# 0146_MTG_HOLES_AND_LABE.net
KiCad netlist of a schematic drawn in Altium Designer
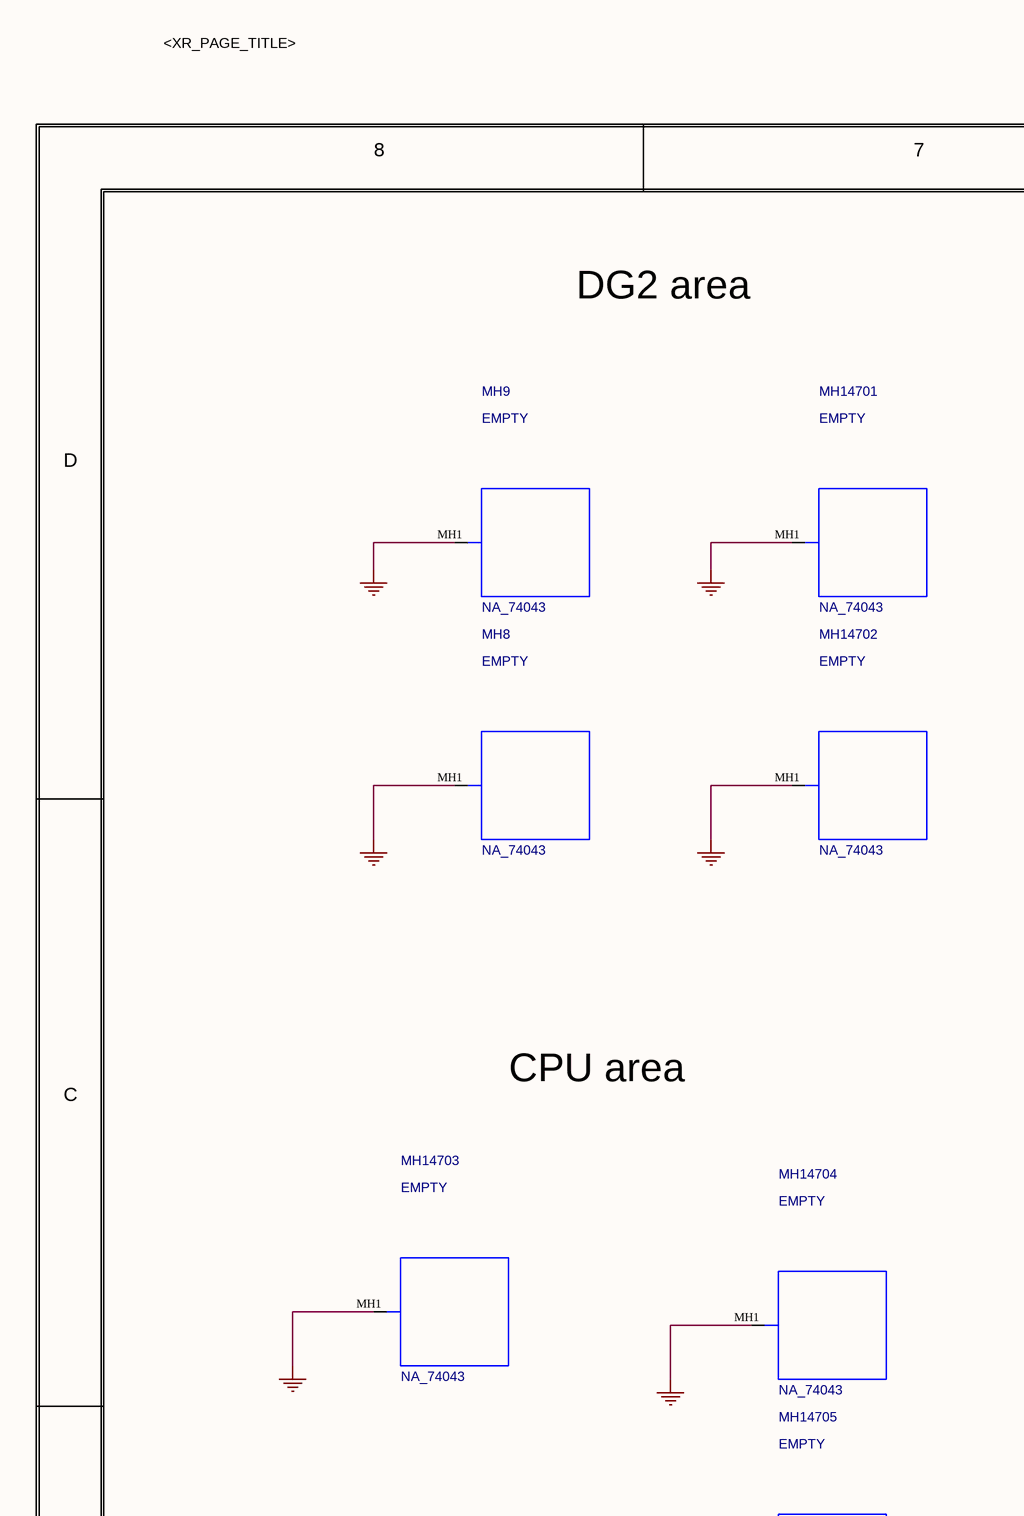
[diagram p0: 0146_MTG HOLES AND LABE.SchDoc, top left]
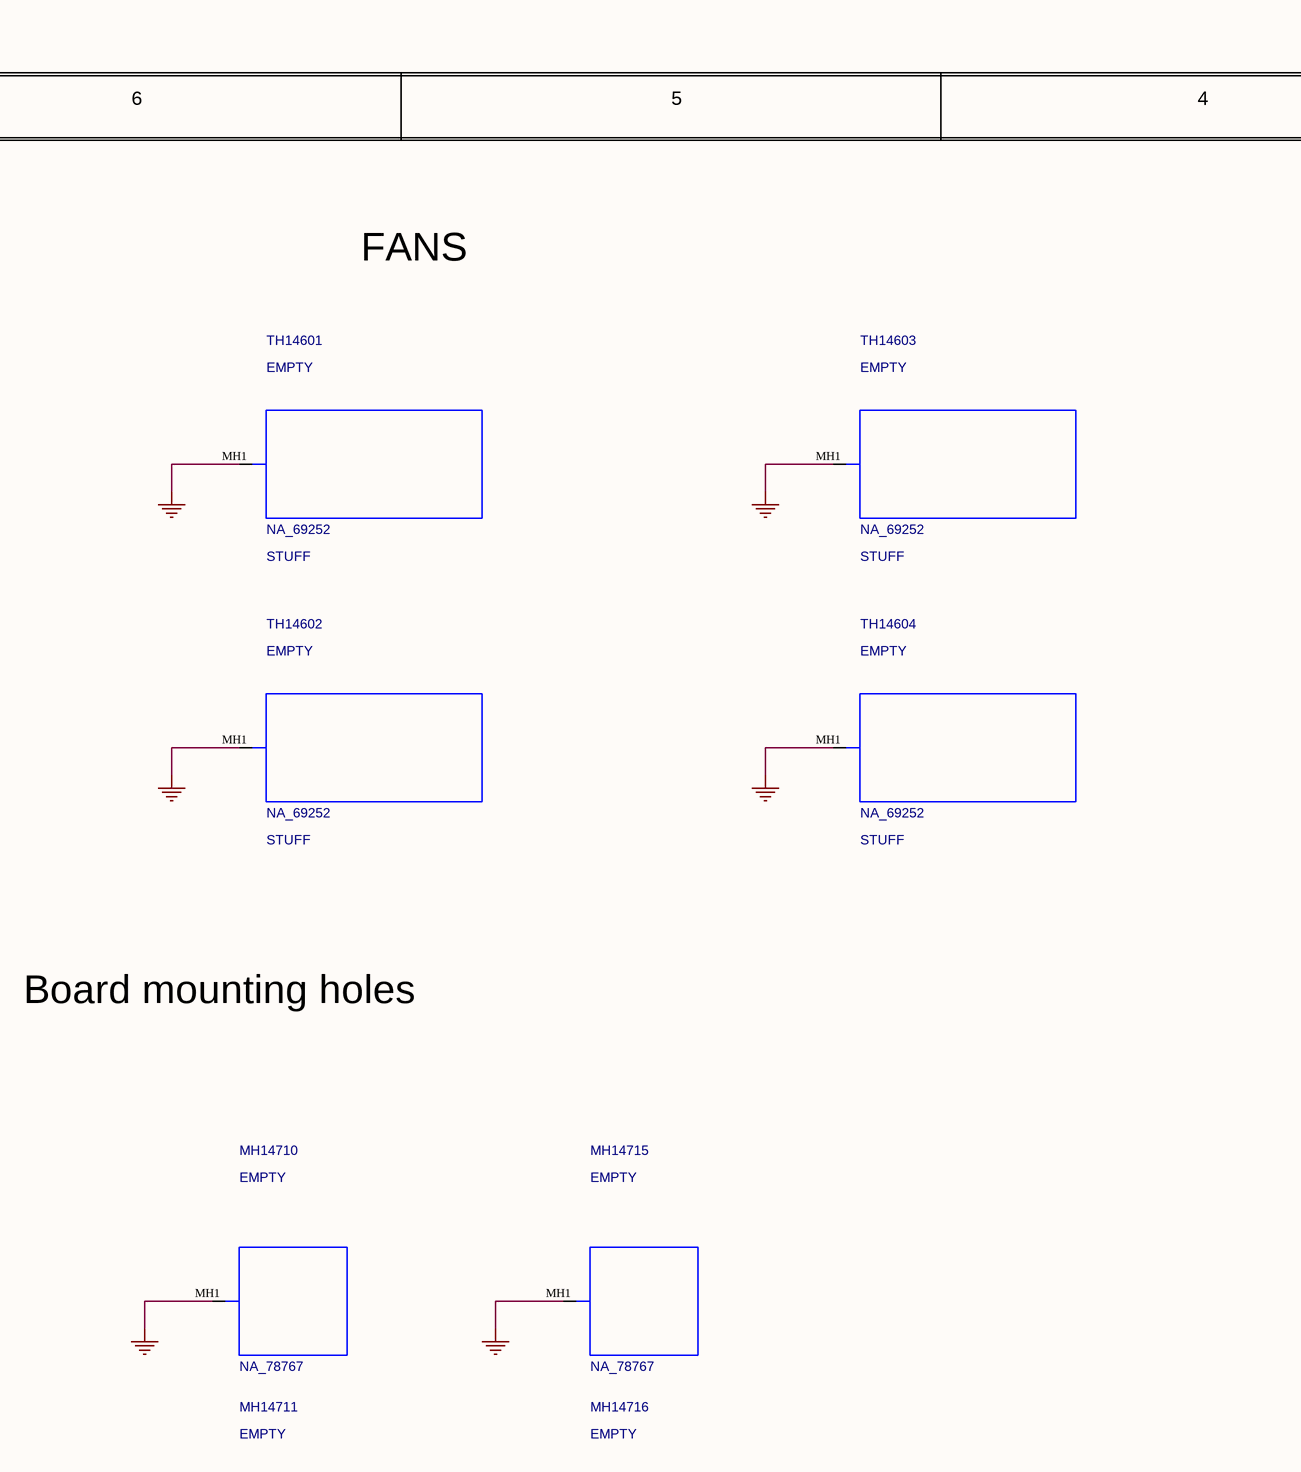
[diagram p1: 0146_MTG HOLES AND LABE.SchDoc, top middle]
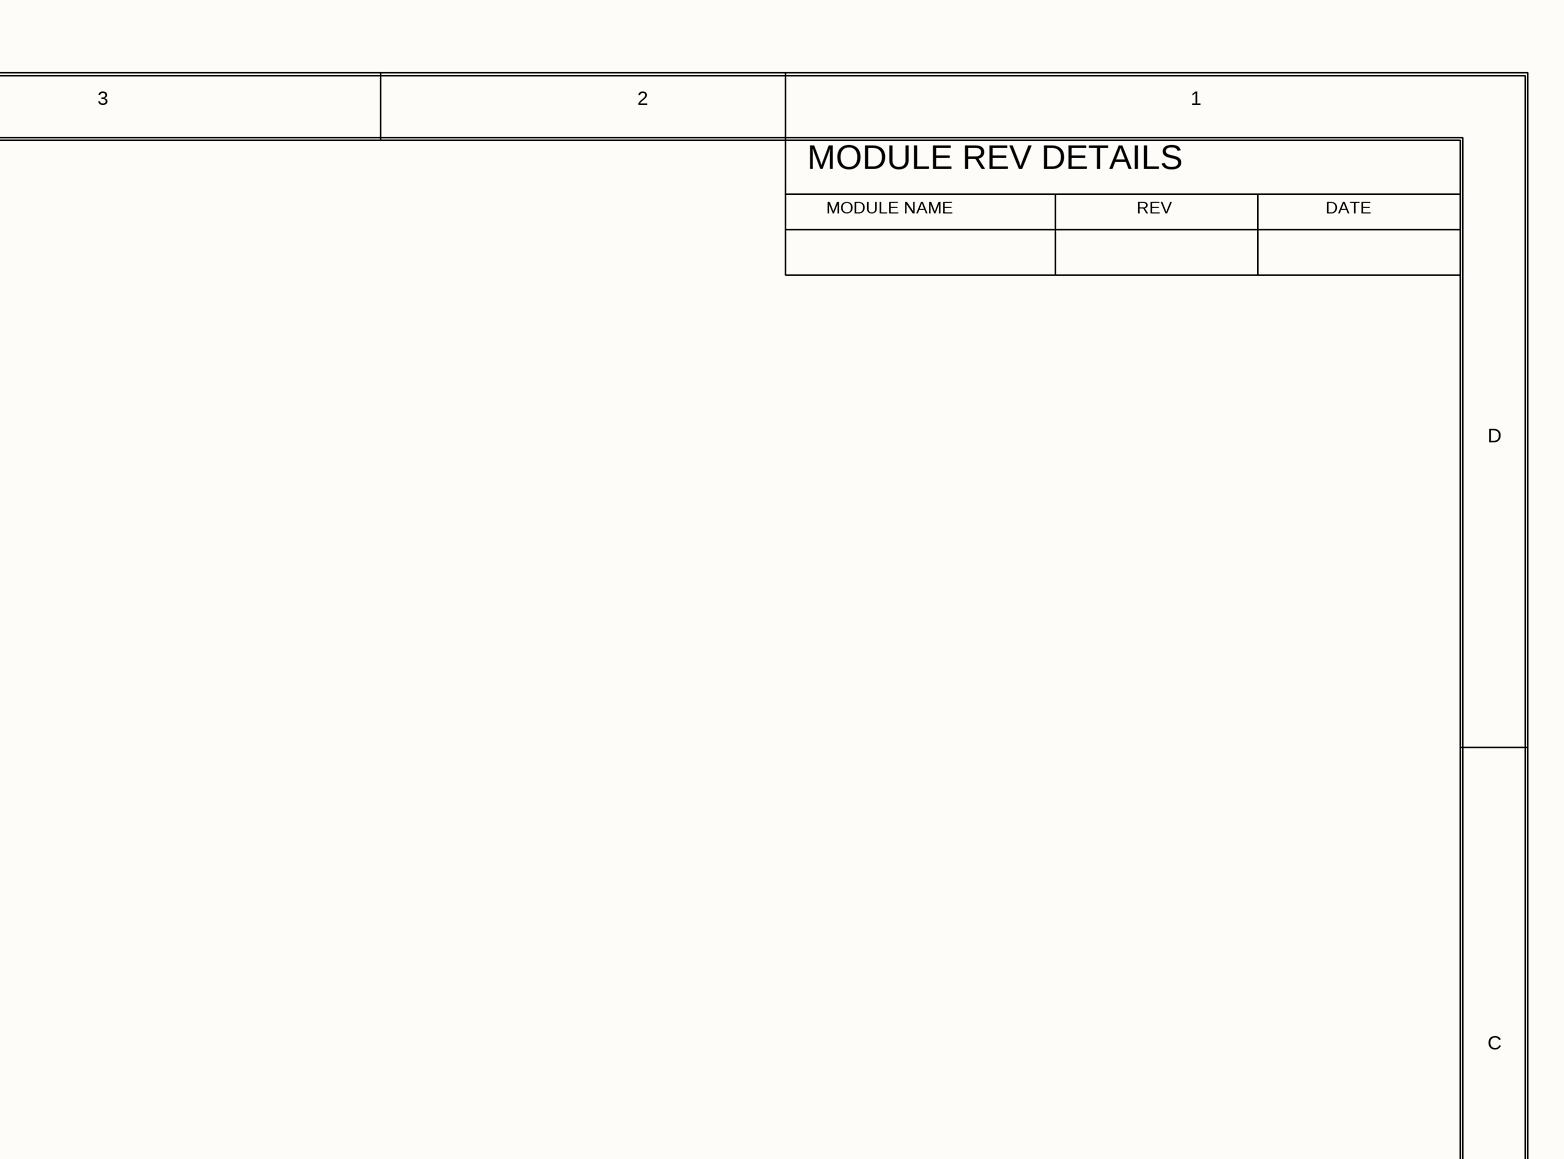
[diagram p2: 0146_MTG HOLES AND LABE.SchDoc, top right]
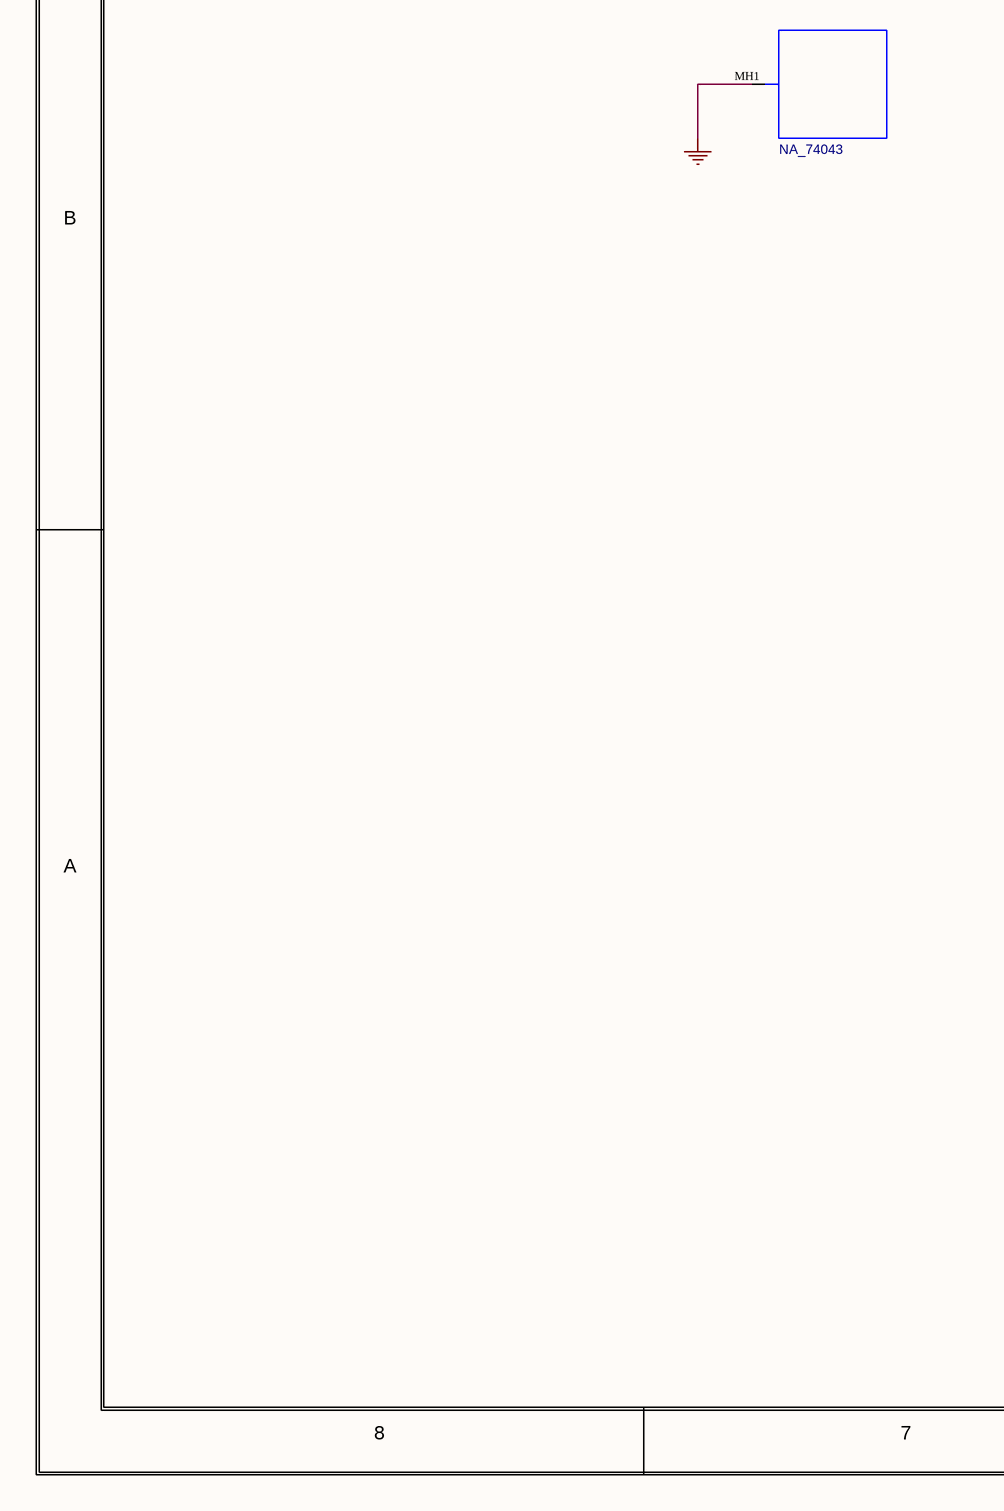
[diagram p3: 0146_MTG HOLES AND LABE.SchDoc, bottom left]
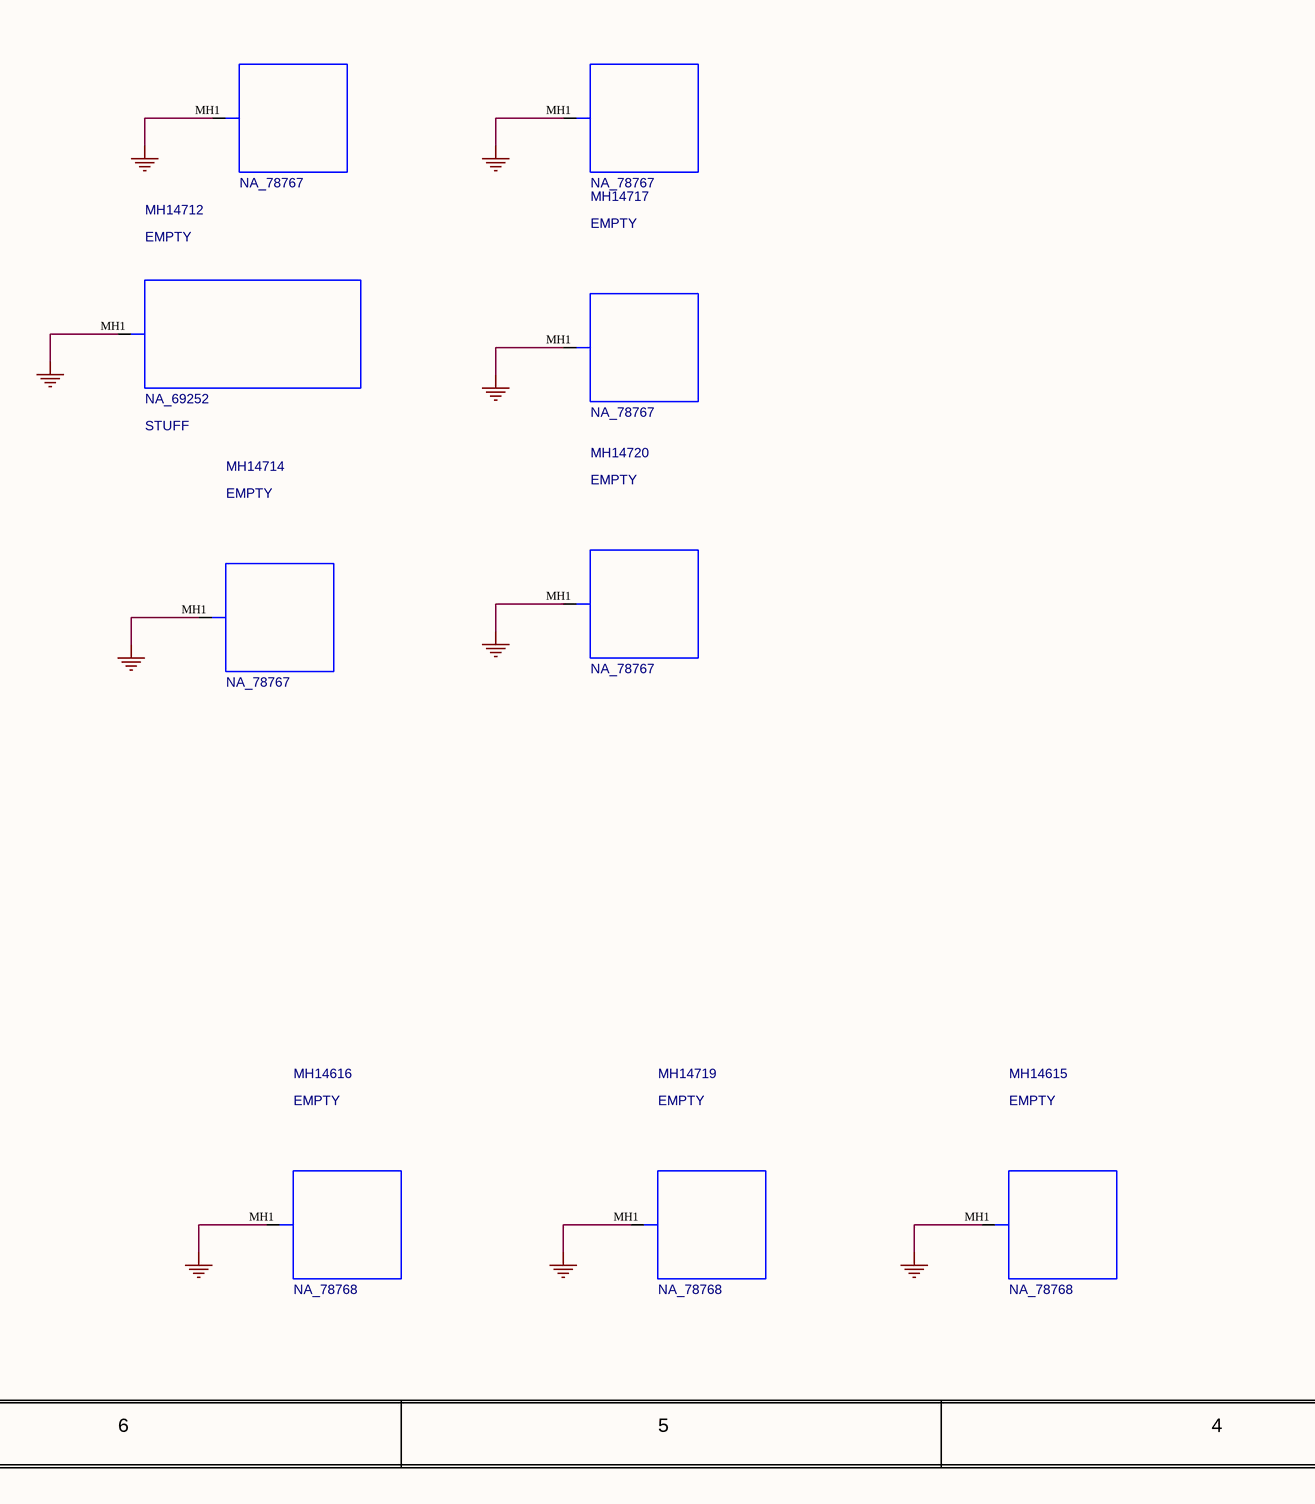
[diagram p4: 0146_MTG HOLES AND LABE.SchDoc, bottom middle]
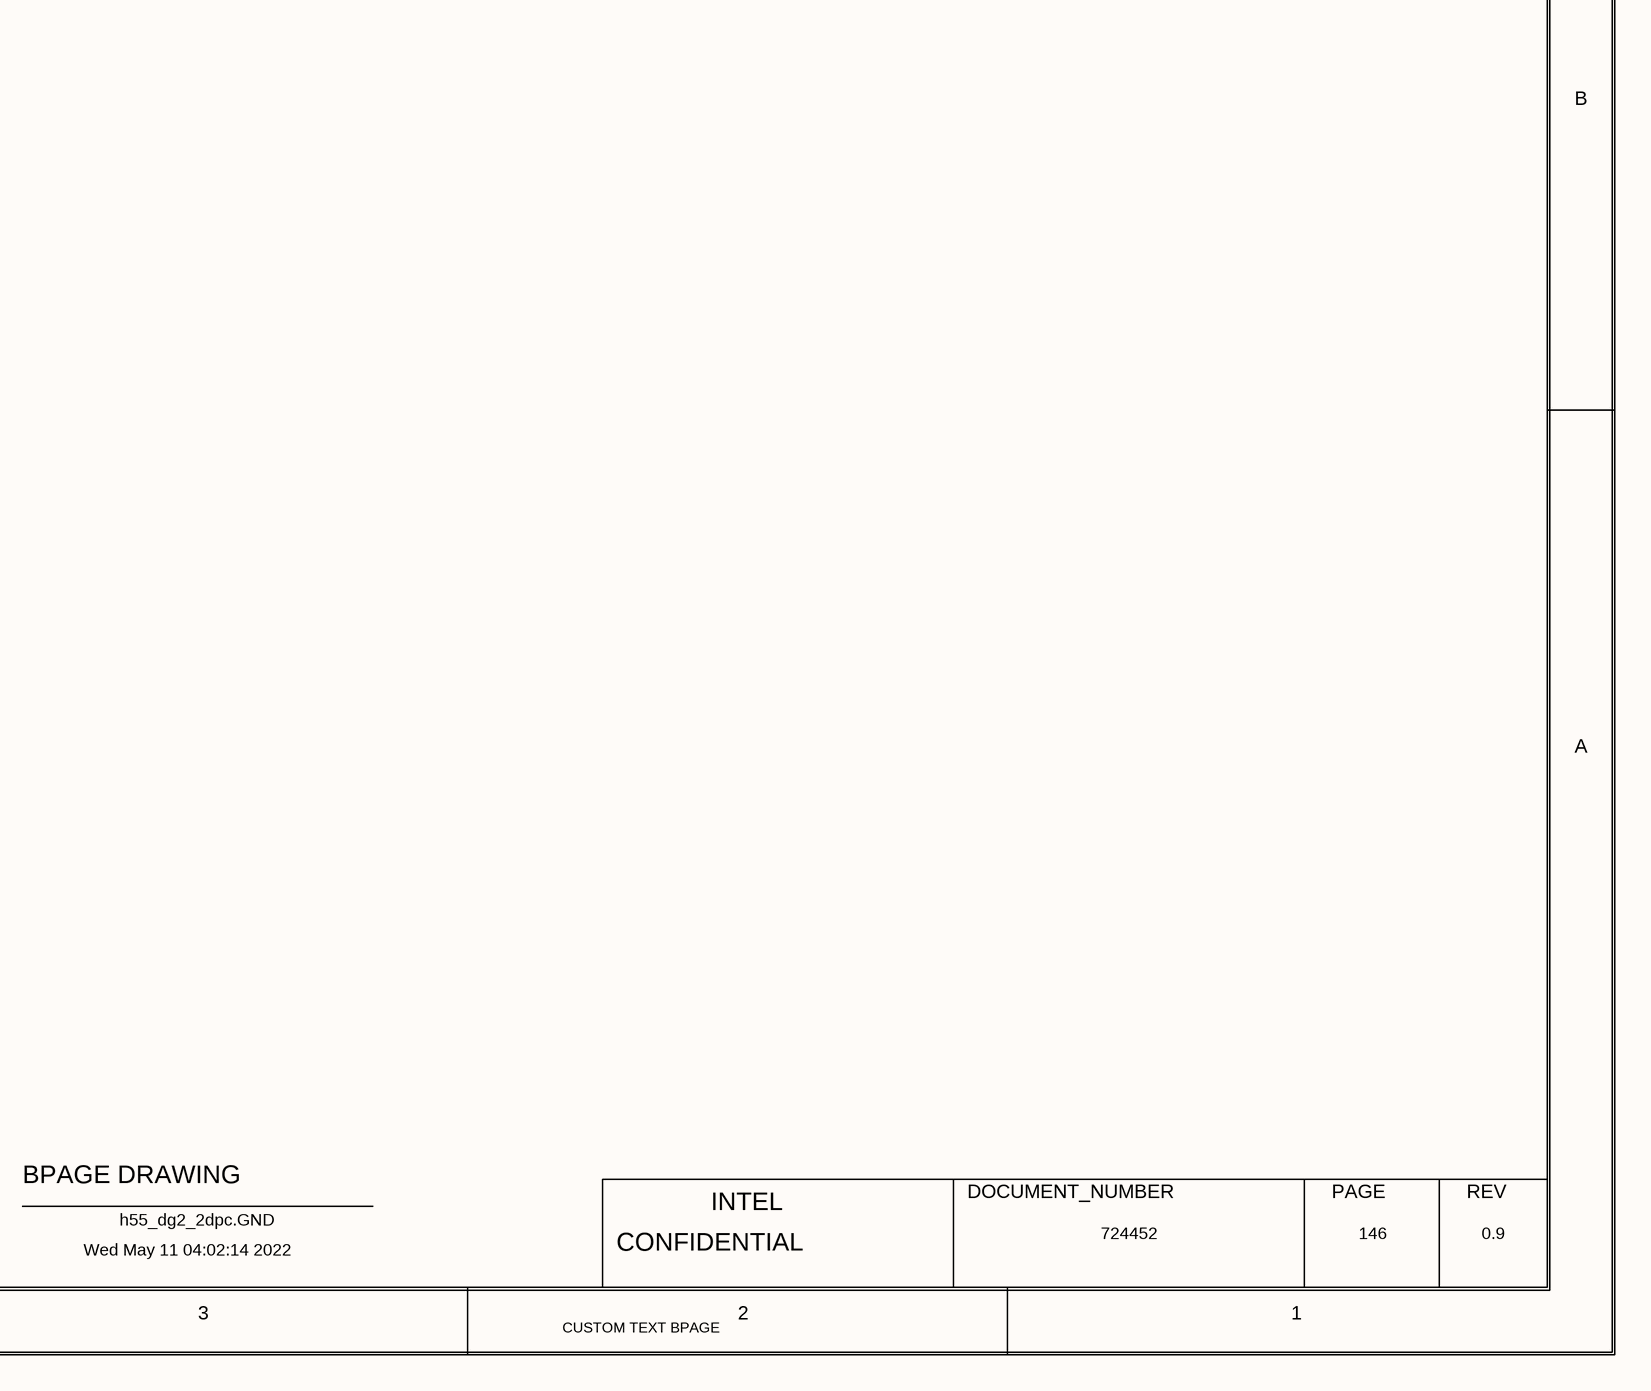
[diagram p5: 0146_MTG HOLES AND LABE.SchDoc, bottom right]

(export (version "E")
  (design (tool "Eeschema 10.0.6"))
  (components
    (comp (ref "MH8")
      (value "C_MTG_HOLE")
      (footprint "CMTG_6500P4200_MA")
      (fields (field (name "MATERIAL") "EMPTY") (field (name "PART_NUMBER") "NA_74043"))
      (libsource (lib "*") (part "C_MTG_HOLE"))
    )
    (comp (ref "MH9")
      (value "C_MTG_HOLE")
      (footprint "CMTG_6500P4200_MA")
      (fields (field (name "MATERIAL") "EMPTY") (field (name "PART_NUMBER") "NA_74043"))
      (libsource (lib "*") (part "C_MTG_HOLE"))
    )
    (comp (ref "MH14615")
      (value "C_MTG_HOLE")
      (footprint "CMTG_8000P2400_MA")
      (fields (field (name "MATERIAL") "EMPTY") (field (name "PART_NUMBER") "NA_78768"))
      (libsource (lib "*") (part "C_MTG_HOLE"))
    )
    (comp (ref "MH14616")
      (value "C_MTG_HOLE")
      (footprint "CMTG_8000P2400_MA")
      (fields (field (name "MATERIAL") "EMPTY") (field (name "PART_NUMBER") "NA_78768"))
      (libsource (lib "*") (part "C_MTG_HOLE"))
    )
    (comp (ref "MH14701")
      (value "C_MTG_HOLE")
      (footprint "CMTG_6500P4200_MA")
      (fields (field (name "MATERIAL") "EMPTY") (field (name "PART_NUMBER") "NA_74043"))
      (libsource (lib "*") (part "C_MTG_HOLE"))
    )
    (comp (ref "MH14702")
      (value "C_MTG_HOLE")
      (footprint "CMTG_6500P4200_MA")
      (fields (field (name "MATERIAL") "EMPTY") (field (name "PART_NUMBER") "NA_74043"))
      (libsource (lib "*") (part "C_MTG_HOLE"))
    )
    (comp (ref "MH14703")
      (value "C_MTG_HOLE")
      (footprint "CMTG_6500P4200_MA")
      (fields (field (name "MATERIAL") "EMPTY") (field (name "PART_NUMBER") "NA_74043"))
      (libsource (lib "*") (part "C_MTG_HOLE"))
    )
    (comp (ref "MH14704")
      (value "C_MTG_HOLE")
      (footprint "CMTG_6500P4200_MA")
      (fields (field (name "MATERIAL") "EMPTY") (field (name "PART_NUMBER") "NA_74043"))
      (libsource (lib "*") (part "C_MTG_HOLE"))
    )
    (comp (ref "MH14705")
      (value "C_MTG_HOLE")
      (footprint "CMTG_6500P4200_MA")
      (fields (field (name "MATERIAL") "EMPTY") (field (name "PART_NUMBER") "NA_74043"))
      (libsource (lib "*") (part "C_MTG_HOLE"))
    )
    (comp (ref "MH14710")
      (value "C_MTG_HOLE")
      (footprint "CMTG_6000P2400_MA")
      (fields (field (name "MATERIAL") "EMPTY") (field (name "PART_NUMBER") "NA_78767"))
      (libsource (lib "*") (part "C_MTG_HOLE"))
    )
    (comp (ref "MH14711")
      (value "C_MTG_HOLE")
      (footprint "CMTG_6000P2400_MA")
      (fields (field (name "MATERIAL") "EMPTY") (field (name "PART_NUMBER") "NA_78767"))
      (libsource (lib "*") (part "C_MTG_HOLE"))
    )
    (comp (ref "MH14712")
      (value "MTG_HOLE_2")
      (footprint "MTG_5000P3500_MA")
      (fields
        (field (name "BOM_USE") "STUFF")
        (field (name "MATERIAL") "EMPTY")
        (field (name "PART_NUMBER") "NA_69252")
      )
      (libsource (lib "*") (part "MTG_HOLE_2"))
    )
    (comp (ref "MH14714")
      (value "C_MTG_HOLE")
      (footprint "CMTG_6000P2400_MA")
      (fields (field (name "MATERIAL") "EMPTY") (field (name "PART_NUMBER") "NA_78767"))
      (libsource (lib "*") (part "C_MTG_HOLE"))
    )
    (comp (ref "MH14715")
      (value "C_MTG_HOLE")
      (footprint "CMTG_6000P2400_MA")
      (fields (field (name "MATERIAL") "EMPTY") (field (name "PART_NUMBER") "NA_78767"))
      (libsource (lib "*") (part "C_MTG_HOLE"))
    )
    (comp (ref "MH14716")
      (value "C_MTG_HOLE")
      (footprint "CMTG_6000P2400_MA")
      (fields (field (name "MATERIAL") "EMPTY") (field (name "PART_NUMBER") "NA_78767"))
      (libsource (lib "*") (part "C_MTG_HOLE"))
    )
    (comp (ref "MH14717")
      (value "C_MTG_HOLE")
      (footprint "CMTG_6000P2400_MA")
      (fields (field (name "MATERIAL") "EMPTY") (field (name "PART_NUMBER") "NA_78767"))
      (libsource (lib "*") (part "C_MTG_HOLE"))
    )
    (comp (ref "MH14719")
      (value "C_MTG_HOLE")
      (footprint "CMTG_8000P2400_MA")
      (fields (field (name "MATERIAL") "EMPTY") (field (name "PART_NUMBER") "NA_78768"))
      (libsource (lib "*") (part "C_MTG_HOLE"))
    )
    (comp (ref "MH14720")
      (value "C_MTG_HOLE")
      (footprint "CMTG_6000P2400_MA")
      (fields (field (name "MATERIAL") "EMPTY") (field (name "PART_NUMBER") "NA_78767"))
      (libsource (lib "*") (part "C_MTG_HOLE"))
    )
    (comp (ref "TH14601")
      (value "MTG_HOLE_2")
      (footprint "MTG_5000P3500_MA")
      (fields
        (field (name "BOM_USE") "STUFF")
        (field (name "MATERIAL") "EMPTY")
        (field (name "PART_NUMBER") "NA_69252")
      )
      (libsource (lib "*") (part "MTG_HOLE_2"))
    )
    (comp (ref "TH14602")
      (value "MTG_HOLE_2")
      (footprint "MTG_5000P3500_MA")
      (fields
        (field (name "BOM_USE") "STUFF")
        (field (name "MATERIAL") "EMPTY")
        (field (name "PART_NUMBER") "NA_69252")
      )
      (libsource (lib "*") (part "MTG_HOLE_2"))
    )
    (comp (ref "TH14603")
      (value "MTG_HOLE_2")
      (footprint "MTG_5000P3500_MA")
      (fields
        (field (name "BOM_USE") "STUFF")
        (field (name "MATERIAL") "EMPTY")
        (field (name "PART_NUMBER") "NA_69252")
      )
      (libsource (lib "*") (part "MTG_HOLE_2"))
    )
    (comp (ref "TH14604")
      (value "MTG_HOLE_2")
      (footprint "MTG_5000P3500_MA")
      (fields
        (field (name "BOM_USE") "STUFF")
        (field (name "MATERIAL") "EMPTY")
        (field (name "PART_NUMBER") "NA_69252")
      )
      (libsource (lib "*") (part "MTG_HOLE_2"))
    )
  )
  (nets
    (net (code "1") (name "GND") (class "Default")
      (node (ref "MH14615") (pin "MH1") (pinfunction "MH1_MH1") (pintype "bidirectional"))
      (node (ref "MH14616") (pin "MH1") (pinfunction "MH1_MH1") (pintype "bidirectional"))
      (node (ref "MH14701") (pin "MH1") (pinfunction "MH1_MH1") (pintype "bidirectional"))
      (node (ref "MH14702") (pin "MH1") (pinfunction "MH1_MH1") (pintype "bidirectional"))
      (node (ref "MH14703") (pin "MH1") (pinfunction "MH1_MH1") (pintype "bidirectional"))
      (node (ref "MH14704") (pin "MH1") (pinfunction "MH1_MH1") (pintype "bidirectional"))
      (node (ref "MH14705") (pin "MH1") (pinfunction "MH1_MH1") (pintype "bidirectional"))
      (node (ref "MH14710") (pin "MH1") (pinfunction "MH1_MH1") (pintype "bidirectional"))
      (node (ref "MH14711") (pin "MH1") (pinfunction "MH1_MH1") (pintype "bidirectional"))
      (node (ref "MH14712") (pin "MH1") (pinfunction "MH1_MH1") (pintype "bidirectional"))
      (node (ref "MH14714") (pin "MH1") (pinfunction "MH1_MH1") (pintype "bidirectional"))
      (node (ref "MH14715") (pin "MH1") (pinfunction "MH1_MH1") (pintype "bidirectional"))
      (node (ref "MH14716") (pin "MH1") (pinfunction "MH1_MH1") (pintype "bidirectional"))
      (node (ref "MH14717") (pin "MH1") (pinfunction "MH1_MH1") (pintype "bidirectional"))
      (node (ref "MH14719") (pin "MH1") (pinfunction "MH1_MH1") (pintype "bidirectional"))
      (node (ref "MH14720") (pin "MH1") (pinfunction "MH1_MH1") (pintype "bidirectional"))
      (node (ref "MH8") (pin "MH1") (pinfunction "MH1_MH1") (pintype "bidirectional"))
      (node (ref "MH9") (pin "MH1") (pinfunction "MH1_MH1") (pintype "bidirectional"))
      (node (ref "TH14601") (pin "MH1") (pinfunction "MH1_MH1") (pintype "bidirectional"))
      (node (ref "TH14602") (pin "MH1") (pinfunction "MH1_MH1") (pintype "bidirectional"))
      (node (ref "TH14603") (pin "MH1") (pinfunction "MH1_MH1") (pintype "bidirectional"))
      (node (ref "TH14604") (pin "MH1") (pinfunction "MH1_MH1") (pintype "bidirectional"))
    )
  )
)
